# UWB_STM32F105.net
KiCad netlist of a schematic drawn in Altium Designer
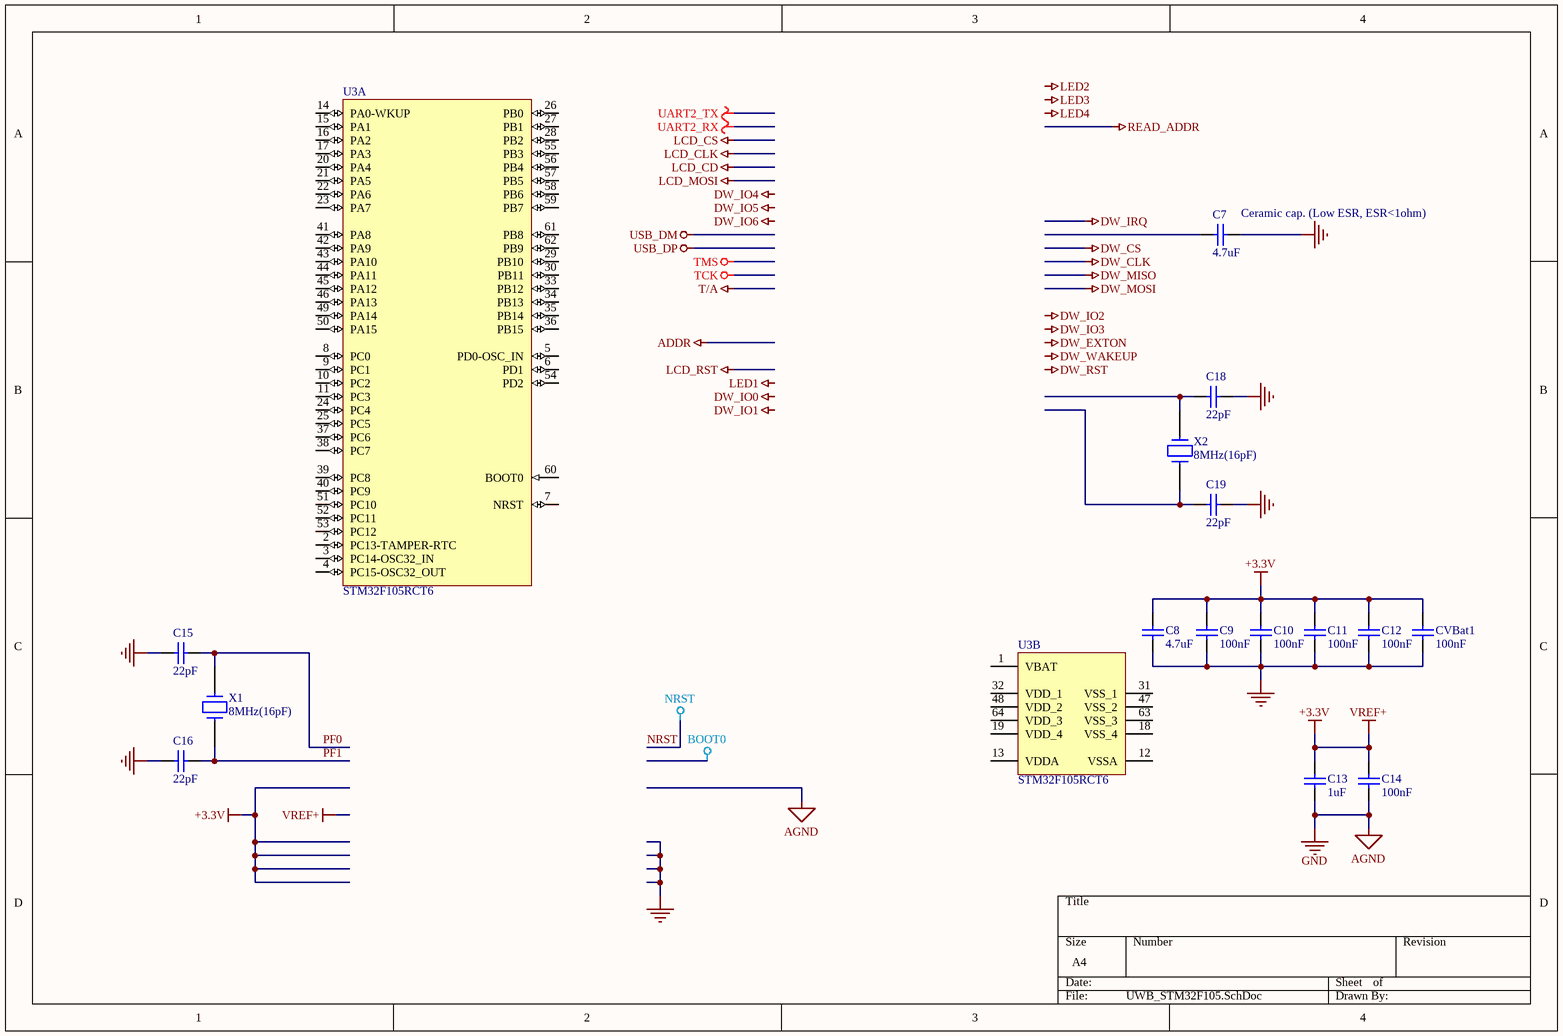
[diagram p0: UWB_STM32F105.SchDoc]

(export (version "E")
  (design (tool "Eeschema 10.0.6"))
  (components
    (comp (ref "C7")
      (value "4.7uF")
      (footprint "CAPC2012L")
      (description "Capacitor")
      (fields (field (name "Comment") "Cap") (field (name "PUBLISHER") "Altium Limited"))
      (libsource (lib "Miscellaneous Devices") (part "Cap"))
    )
    (comp (ref "C8")
      (value "4.7uF")
      (footprint "CAPC2012L")
      (description "Capacitor")
      (fields (field (name "Comment") "Cap") (field (name "PUBLISHER") "Altium Limited"))
      (libsource (lib "Miscellaneous Devices") (part "Cap"))
    )
    (comp (ref "C9")
      (value "100nF")
      (footprint "CAPC1608L")
      (description "Capacitor")
      (fields (field (name "Comment") "Cap") (field (name "PUBLISHER") "Altium Limited"))
      (libsource (lib "Miscellaneous Devices") (part "Cap"))
    )
    (comp (ref "C10")
      (value "100nF")
      (footprint "CAPC1608L")
      (description "Capacitor")
      (fields (field (name "Comment") "Cap") (field (name "PUBLISHER") "Altium Limited"))
      (libsource (lib "Miscellaneous Devices") (part "Cap"))
    )
    (comp (ref "C11")
      (value "100nF")
      (footprint "CAPC1608L")
      (description "Capacitor")
      (fields (field (name "Comment") "Cap") (field (name "PUBLISHER") "Altium Limited"))
      (libsource (lib "Miscellaneous Devices") (part "Cap"))
    )
    (comp (ref "C12")
      (value "100nF")
      (footprint "CAPC1608L")
      (description "Capacitor")
      (fields (field (name "Comment") "Cap") (field (name "PUBLISHER") "Altium Limited"))
      (libsource (lib "Miscellaneous Devices") (part "Cap"))
    )
    (comp (ref "C13")
      (value "1uF")
      (footprint "CAPC1608L")
      (description "Capacitor")
      (fields (field (name "Comment") "Cap") (field (name "PUBLISHER") "Altium Limited"))
      (libsource (lib "Miscellaneous Devices") (part "Cap"))
    )
    (comp (ref "C14")
      (value "100nF")
      (footprint "CAPC1608L")
      (description "Capacitor")
      (fields (field (name "Comment") "Cap") (field (name "PUBLISHER") "Altium Limited"))
      (libsource (lib "Miscellaneous Devices") (part "Cap"))
    )
    (comp (ref "C15")
      (value "22pF")
      (footprint "CAPC1608L")
      (description "Capacitor")
      (fields (field (name "Comment") "Cap") (field (name "PUBLISHER") "Altium Limited"))
      (libsource (lib "Miscellaneous Devices") (part "Cap"))
    )
    (comp (ref "C16")
      (value "22pF")
      (footprint "CAPC1608L")
      (description "Capacitor")
      (fields (field (name "Comment") "Cap") (field (name "PUBLISHER") "Altium Limited"))
      (libsource (lib "Miscellaneous Devices") (part "Cap"))
    )
    (comp (ref "C18")
      (value "22pF")
      (footprint "CAPC1608L")
      (description "Capacitor")
      (fields (field (name "Comment") "Cap") (field (name "PUBLISHER") "Altium Limited"))
      (libsource (lib "Miscellaneous Devices") (part "Cap"))
    )
    (comp (ref "C19")
      (value "22pF")
      (footprint "CAPC1608L")
      (description "Capacitor")
      (fields (field (name "Comment") "Cap") (field (name "PUBLISHER") "Altium Limited"))
      (libsource (lib "Miscellaneous Devices") (part "Cap"))
    )
    (comp (ref "CVBat1")
      (value "100nF")
      (footprint "CAPC1608L")
      (description "Capacitor")
      (fields (field (name "Comment") "Cap") (field (name "PUBLISHER") "Altium Limited"))
      (libsource (lib "Miscellaneous Devices") (part "Cap"))
    )
    (comp (ref "U3")
      (value "STM32F105RCT6")
      (footprint "LQFP64_N")
      (libsource (lib "STMicroelectronics STM32 F1") (part "STM32F105RCT6"))
    )
    (comp (ref "X1")
      (value "8MHz(16pF)")
      (footprint "XTAL ABM7")
      (description "Crystal")
      (libsource (lib "*") (part "CRYSTAL"))
    )
    (comp (ref "X2")
      (value "8MHz(16pF)")
      (footprint "XTAL ABS13")
      (description "Crystal")
      (libsource (lib "*") (part "CRYSTAL"))
    )
  )
  (nets
    (net (code "1") (name "+3.3V") (class "Default")
      (node (ref "C10") (pin "2") (pinfunction "2_2") (pintype "passive"))
      (node (ref "C11") (pin "2") (pinfunction "2_2") (pintype "passive"))
      (node (ref "C12") (pin "2") (pinfunction "2_2") (pintype "passive"))
      (node (ref "C13") (pin "2") (pinfunction "2_2") (pintype "passive"))
      (node (ref "C14") (pin "2") (pinfunction "2_2") (pintype "passive"))
      (node (ref "C8") (pin "2") (pinfunction "2_2") (pintype "passive"))
      (node (ref "C9") (pin "2") (pinfunction "2_2") (pintype "passive"))
      (node (ref "CVBat1") (pin "2") (pinfunction "2_2") (pintype "passive"))
    )
    (net (code "2") (name "/PF0") (class "Default")
      (node (ref "C15") (pin "1") (pinfunction "1_1") (pintype "passive"))
      (node (ref "X1") (pin "2") (pinfunction "2_2") (pintype "passive"))
    )
    (net (code "3") (name "/PF1") (class "Default")
      (node (ref "C16") (pin "1") (pinfunction "1_1") (pintype "passive"))
      (node (ref "X1") (pin "1") (pinfunction "1_1") (pintype "passive"))
    )
    (net (code "5") (name "AGND") (class "Default")
      (node (ref "C10") (pin "1") (pinfunction "1_1") (pintype "passive"))
      (node (ref "C11") (pin "1") (pinfunction "1_1") (pintype "passive"))
      (node (ref "C12") (pin "1") (pinfunction "1_1") (pintype "passive"))
      (node (ref "C13") (pin "1") (pinfunction "1_1") (pintype "passive"))
      (node (ref "C14") (pin "1") (pinfunction "1_1") (pintype "passive"))
      (node (ref "C15") (pin "2") (pinfunction "2_2") (pintype "passive"))
      (node (ref "C16") (pin "2") (pinfunction "2_2") (pintype "passive"))
      (node (ref "C18") (pin "2") (pinfunction "2_2") (pintype "passive"))
      (node (ref "C19") (pin "2") (pinfunction "2_2") (pintype "passive"))
      (node (ref "C7") (pin "1") (pinfunction "1_1") (pintype "passive"))
      (node (ref "C8") (pin "1") (pinfunction "1_1") (pintype "passive"))
      (node (ref "C9") (pin "1") (pinfunction "1_1") (pintype "passive"))
      (node (ref "CVBat1") (pin "1") (pinfunction "1_1") (pintype "passive"))
    )
    (net (code "32") (name "Net-(C18-Pad1)") (class "Default")
      (node (ref "C18") (pin "1") (pinfunction "1_1") (pintype "passive"))
      (node (ref "X2") (pin "1") (pinfunction "1_1") (pintype "passive"))
    )
    (net (code "33") (name "Net-(C19-Pad1)") (class "Default")
      (node (ref "C19") (pin "1") (pinfunction "1_1") (pintype "passive"))
      (node (ref "X2") (pin "2") (pinfunction "2_2") (pintype "passive"))
    )
    (net (code "41") (name "unconnected-(C7-Pad2)") (class "Default")
      (node (ref "C7") (pin "2") (pinfunction "2_2") (pintype "passive"))
    )
    (net (code "42") (name "unconnected-(U3A-BOOT0-Pad60)") (class "Default")
      (node (ref "U3") (pin "60") (pinfunction "BOOT0_60") (pintype "input"))
    )
    (net (code "43") (name "unconnected-(U3A-NRST-Pad7)") (class "Default")
      (node (ref "U3") (pin "7") (pinfunction "NRST_7") (pintype "bidirectional"))
    )
    (net (code "44") (name "unconnected-(U3A-PA0-WKUP-Pad14)") (class "Default")
      (node (ref "U3") (pin "14") (pinfunction "PA0-WKUP_14") (pintype "bidirectional"))
    )
    (net (code "45") (name "unconnected-(U3A-PA1-Pad15)") (class "Default")
      (node (ref "U3") (pin "15") (pinfunction "PA1_15") (pintype "bidirectional"))
    )
    (net (code "46") (name "unconnected-(U3A-PA2-Pad16)") (class "Default")
      (node (ref "U3") (pin "16") (pinfunction "PA2_16") (pintype "bidirectional"))
    )
    (net (code "47") (name "unconnected-(U3A-PA3-Pad17)") (class "Default")
      (node (ref "U3") (pin "17") (pinfunction "PA3_17") (pintype "bidirectional"))
    )
    (net (code "48") (name "unconnected-(U3A-PA4-Pad20)") (class "Default")
      (node (ref "U3") (pin "20") (pinfunction "PA4_20") (pintype "bidirectional"))
    )
    (net (code "49") (name "unconnected-(U3A-PA5-Pad21)") (class "Default")
      (node (ref "U3") (pin "21") (pinfunction "PA5_21") (pintype "bidirectional"))
    )
    (net (code "50") (name "unconnected-(U3A-PA6-Pad22)") (class "Default")
      (node (ref "U3") (pin "22") (pinfunction "PA6_22") (pintype "bidirectional"))
    )
    (net (code "51") (name "unconnected-(U3A-PA7-Pad23)") (class "Default")
      (node (ref "U3") (pin "23") (pinfunction "PA7_23") (pintype "bidirectional"))
    )
    (net (code "52") (name "unconnected-(U3A-PA8-Pad41)") (class "Default")
      (node (ref "U3") (pin "41") (pinfunction "PA8_41") (pintype "bidirectional"))
    )
    (net (code "53") (name "unconnected-(U3A-PA9-Pad42)") (class "Default")
      (node (ref "U3") (pin "42") (pinfunction "PA9_42") (pintype "bidirectional"))
    )
    (net (code "54") (name "unconnected-(U3A-PA10-Pad43)") (class "Default")
      (node (ref "U3") (pin "43") (pinfunction "PA10_43") (pintype "bidirectional"))
    )
    (net (code "55") (name "unconnected-(U3A-PA11-Pad44)") (class "Default")
      (node (ref "U3") (pin "44") (pinfunction "PA11_44") (pintype "bidirectional"))
    )
    (net (code "56") (name "unconnected-(U3A-PA12-Pad45)") (class "Default")
      (node (ref "U3") (pin "45") (pinfunction "PA12_45") (pintype "bidirectional"))
    )
    (net (code "57") (name "unconnected-(U3A-PA13-Pad46)") (class "Default")
      (node (ref "U3") (pin "46") (pinfunction "PA13_46") (pintype "bidirectional"))
    )
    (net (code "58") (name "unconnected-(U3A-PA14-Pad49)") (class "Default")
      (node (ref "U3") (pin "49") (pinfunction "PA14_49") (pintype "bidirectional"))
    )
    (net (code "59") (name "unconnected-(U3A-PA15-Pad50)") (class "Default")
      (node (ref "U3") (pin "50") (pinfunction "PA15_50") (pintype "bidirectional"))
    )
    (net (code "60") (name "unconnected-(U3A-PB0-Pad26)") (class "Default")
      (node (ref "U3") (pin "26") (pinfunction "PB0_26") (pintype "bidirectional"))
    )
    (net (code "61") (name "unconnected-(U3A-PB1-Pad27)") (class "Default")
      (node (ref "U3") (pin "27") (pinfunction "PB1_27") (pintype "bidirectional"))
    )
    (net (code "62") (name "unconnected-(U3A-PB2-Pad28)") (class "Default")
      (node (ref "U3") (pin "28") (pinfunction "PB2_28") (pintype "bidirectional"))
    )
    (net (code "63") (name "unconnected-(U3A-PB3-Pad55)") (class "Default")
      (node (ref "U3") (pin "55") (pinfunction "PB3_55") (pintype "bidirectional"))
    )
    (net (code "64") (name "unconnected-(U3A-PB4-Pad56)") (class "Default")
      (node (ref "U3") (pin "56") (pinfunction "PB4_56") (pintype "bidirectional"))
    )
    (net (code "65") (name "unconnected-(U3A-PB5-Pad57)") (class "Default")
      (node (ref "U3") (pin "57") (pinfunction "PB5_57") (pintype "bidirectional"))
    )
    (net (code "66") (name "unconnected-(U3A-PB6-Pad58)") (class "Default")
      (node (ref "U3") (pin "58") (pinfunction "PB6_58") (pintype "bidirectional"))
    )
    (net (code "67") (name "unconnected-(U3A-PB7-Pad59)") (class "Default")
      (node (ref "U3") (pin "59") (pinfunction "PB7_59") (pintype "bidirectional"))
    )
    (net (code "68") (name "unconnected-(U3A-PB8-Pad61)") (class "Default")
      (node (ref "U3") (pin "61") (pinfunction "PB8_61") (pintype "bidirectional"))
    )
    (net (code "69") (name "unconnected-(U3A-PB9-Pad62)") (class "Default")
      (node (ref "U3") (pin "62") (pinfunction "PB9_62") (pintype "bidirectional"))
    )
    (net (code "70") (name "unconnected-(U3A-PB10-Pad29)") (class "Default")
      (node (ref "U3") (pin "29") (pinfunction "PB10_29") (pintype "bidirectional"))
    )
    (net (code "71") (name "unconnected-(U3A-PB11-Pad30)") (class "Default")
      (node (ref "U3") (pin "30") (pinfunction "PB11_30") (pintype "bidirectional"))
    )
    (net (code "72") (name "unconnected-(U3A-PB12-Pad33)") (class "Default")
      (node (ref "U3") (pin "33") (pinfunction "PB12_33") (pintype "bidirectional"))
    )
    (net (code "73") (name "unconnected-(U3A-PB13-Pad34)") (class "Default")
      (node (ref "U3") (pin "34") (pinfunction "PB13_34") (pintype "bidirectional"))
    )
    (net (code "74") (name "unconnected-(U3A-PB14-Pad35)") (class "Default")
      (node (ref "U3") (pin "35") (pinfunction "PB14_35") (pintype "bidirectional"))
    )
    (net (code "75") (name "unconnected-(U3A-PB15-Pad36)") (class "Default")
      (node (ref "U3") (pin "36") (pinfunction "PB15_36") (pintype "bidirectional"))
    )
    (net (code "76") (name "unconnected-(U3A-PC0-Pad8)") (class "Default")
      (node (ref "U3") (pin "8") (pinfunction "PC0_8") (pintype "bidirectional"))
    )
    (net (code "77") (name "unconnected-(U3A-PC1-Pad9)") (class "Default")
      (node (ref "U3") (pin "9") (pinfunction "PC1_9") (pintype "bidirectional"))
    )
    (net (code "78") (name "unconnected-(U3A-PC2-Pad10)") (class "Default")
      (node (ref "U3") (pin "10") (pinfunction "PC2_10") (pintype "bidirectional"))
    )
    (net (code "79") (name "unconnected-(U3A-PC3-Pad11)") (class "Default")
      (node (ref "U3") (pin "11") (pinfunction "PC3_11") (pintype "bidirectional"))
    )
    (net (code "80") (name "unconnected-(U3A-PC4-Pad24)") (class "Default")
      (node (ref "U3") (pin "24") (pinfunction "PC4_24") (pintype "bidirectional"))
    )
    (net (code "81") (name "unconnected-(U3A-PC5-Pad25)") (class "Default")
      (node (ref "U3") (pin "25") (pinfunction "PC5_25") (pintype "bidirectional"))
    )
    (net (code "82") (name "unconnected-(U3A-PC6-Pad37)") (class "Default")
      (node (ref "U3") (pin "37") (pinfunction "PC6_37") (pintype "bidirectional"))
    )
    (net (code "83") (name "unconnected-(U3A-PC7-Pad38)") (class "Default")
      (node (ref "U3") (pin "38") (pinfunction "PC7_38") (pintype "bidirectional"))
    )
    (net (code "84") (name "unconnected-(U3A-PC8-Pad39)") (class "Default")
      (node (ref "U3") (pin "39") (pinfunction "PC8_39") (pintype "bidirectional"))
    )
    (net (code "85") (name "unconnected-(U3A-PC9-Pad40)") (class "Default")
      (node (ref "U3") (pin "40") (pinfunction "PC9_40") (pintype "bidirectional"))
    )
    (net (code "86") (name "unconnected-(U3A-PC10-Pad51)") (class "Default")
      (node (ref "U3") (pin "51") (pinfunction "PC10_51") (pintype "bidirectional"))
    )
    (net (code "87") (name "unconnected-(U3A-PC11-Pad52)") (class "Default")
      (node (ref "U3") (pin "52") (pinfunction "PC11_52") (pintype "bidirectional"))
    )
    (net (code "88") (name "unconnected-(U3A-PC12-Pad53)") (class "Default")
      (node (ref "U3") (pin "53") (pinfunction "PC12_53") (pintype "bidirectional"))
    )
    (net (code "89") (name "unconnected-(U3A-PC13-TAMPER-RTC-Pad2)") (class "Default")
      (node (ref "U3") (pin "2") (pinfunction "PC13-TAMPER-RTC_2") (pintype "bidirectional"))
    )
    (net (code "90") (name "unconnected-(U3A-PC14-OSC32_IN-Pad3)") (class "Default")
      (node (ref "U3") (pin "3") (pinfunction "PC14-OSC32_IN_3") (pintype "bidirectional"))
    )
    (net (code "91") (name "unconnected-(U3A-PC15-OSC32_OUT-Pad4)") (class "Default")
      (node (ref "U3") (pin "4") (pinfunction "PC15-OSC32_OUT_4") (pintype "bidirectional"))
    )
    (net (code "92") (name "unconnected-(U3A-PD0-OSC_IN-Pad5)") (class "Default")
      (node (ref "U3") (pin "5") (pinfunction "PD0-OSC_IN_5") (pintype "bidirectional"))
    )
    (net (code "93") (name "unconnected-(U3A-PD1-Pad6)") (class "Default")
      (node (ref "U3") (pin "6") (pinfunction "PD1_6") (pintype "bidirectional"))
    )
    (net (code "94") (name "unconnected-(U3A-PD2-Pad54)") (class "Default")
      (node (ref "U3") (pin "54") (pinfunction "PD2_54") (pintype "bidirectional"))
    )
    (net (code "95") (name "unconnected-(U3B-VBAT-Pad1)") (class "Default")
      (node (ref "U3") (pin "1") (pinfunction "VBAT_1") (pintype "power_in"))
    )
    (net (code "96") (name "unconnected-(U3B-VDDA-Pad13)") (class "Default")
      (node (ref "U3") (pin "13") (pinfunction "VDDA_13") (pintype "power_in"))
    )
    (net (code "97") (name "unconnected-(U3B-VDD_1-Pad32)") (class "Default")
      (node (ref "U3") (pin "32") (pinfunction "VDD_1_32") (pintype "power_in"))
    )
    (net (code "98") (name "unconnected-(U3B-VDD_2-Pad48)") (class "Default")
      (node (ref "U3") (pin "48") (pinfunction "VDD_2_48") (pintype "power_in"))
    )
    (net (code "99") (name "unconnected-(U3B-VDD_3-Pad64)") (class "Default")
      (node (ref "U3") (pin "64") (pinfunction "VDD_3_64") (pintype "power_in"))
    )
    (net (code "100") (name "unconnected-(U3B-VDD_4-Pad19)") (class "Default")
      (node (ref "U3") (pin "19") (pinfunction "VDD_4_19") (pintype "power_in"))
    )
    (net (code "101") (name "unconnected-(U3B-VSSA-Pad12)") (class "Default")
      (node (ref "U3") (pin "12") (pinfunction "VSSA_12") (pintype "power_in"))
    )
    (net (code "102") (name "unconnected-(U3B-VSS_1-Pad31)") (class "Default")
      (node (ref "U3") (pin "31") (pinfunction "VSS_1_31") (pintype "power_in"))
    )
    (net (code "103") (name "unconnected-(U3B-VSS_2-Pad47)") (class "Default")
      (node (ref "U3") (pin "47") (pinfunction "VSS_2_47") (pintype "power_in"))
    )
    (net (code "104") (name "unconnected-(U3B-VSS_3-Pad63)") (class "Default")
      (node (ref "U3") (pin "63") (pinfunction "VSS_3_63") (pintype "power_in"))
    )
    (net (code "105") (name "unconnected-(U3B-VSS_4-Pad18)") (class "Default")
      (node (ref "U3") (pin "18") (pinfunction "VSS_4_18") (pintype "power_in"))
    )
  )
)
